# single-pwm.net
KiCad netlist of a schematic drawn in Altium Designer
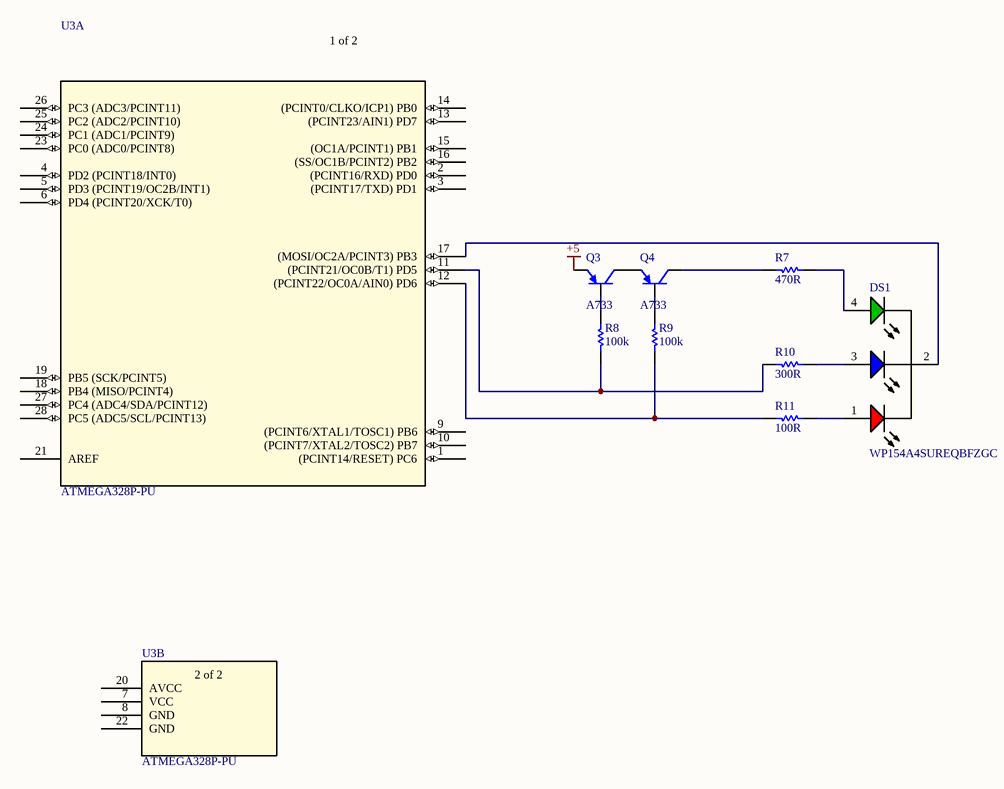
[diagram p0: single-pwm.SchDoc]

(export (version "E")
  (design (tool "Eeschema 10.0.6"))
  (components
    (comp (ref "DS1")
      (value "WP154A4SUREQBFZGC")
      (footprint "KING-WP154A4SUREQBFZGC_V")
      (description "Full Color LED Lamp, Dominant Wavelength RGB 630 / 525 / 465 nm, -40 to 85 degC, 4-Pin THD, RoHS")
      (fields (field (name "MANUFACTURER") "Kingbright"))
      (libsource (lib "Altium Content Vault") (part "LED-RGB-AKAA-4"))
    )
    (comp (ref "Q3")
      (value "A733")
      (footprint "TO-92_ONS")
      (description "PNP General Purpose Transistor")
      (fields (field (name "PUBLISHER") "Altium Limited"))
      (libsource (lib "Common Parts") (part "A733"))
    )
    (comp (ref "Q4")
      (value "A733")
      (footprint "TO-92_ONS")
      (description "PNP General Purpose Transistor")
      (fields (field (name "PUBLISHER") "Altium Limited"))
      (libsource (lib "Common Parts") (part "A733"))
    )
    (comp (ref "R7")
      (value "470R")
      (footprint "RES_TOP_1")
      (description "Resistor")
      (fields (field (name "PUBLISHER") "Altium Limited"))
      (libsource (lib "Common Parts") (part "Res1"))
    )
    (comp (ref "R8")
      (value "100k")
      (footprint "RES_TOP_1")
      (description "Resistor")
      (fields (field (name "PUBLISHER") "Altium Limited"))
      (libsource (lib "Common Parts") (part "Res1"))
    )
    (comp (ref "R9")
      (value "100k")
      (footprint "RES_TOP_1")
      (description "Resistor")
      (fields (field (name "PUBLISHER") "Altium Limited"))
      (libsource (lib "Common Parts") (part "Res1"))
    )
    (comp (ref "R10")
      (value "300R")
      (footprint "RES_TOP_1")
      (description "Resistor")
      (fields (field (name "PUBLISHER") "Altium Limited"))
      (libsource (lib "Common Parts") (part "Res1"))
    )
    (comp (ref "R11")
      (value "100R")
      (footprint "RES_TOP_1")
      (description "Resistor")
      (fields (field (name "PUBLISHER") "Altium Limited"))
      (libsource (lib "Common Parts") (part "Res1"))
    )
    (comp (ref "U3")
      (value "ATMEGA328P-PU")
      (footprint "28P3_ATM")
      (description "No Description Available")
      (fields (field (name "COPYRIGHT") "Copyright (C) 2018 Accelerated Designs. All rights reserved"))
      (libsource (lib "ul_ATMEGA328PPU") (part "ATMEGA328P-PU"))
    )
  )
  (nets
    (net (code "1") (name "+5") (class "Default")
      (node (ref "Q3") (pin "1") (pinfunction "E_1") (pintype "passive"))
    )
    (net (code "2") (name "Net-(DS1-BLUE)") (class "Default")
      (node (ref "DS1") (pin "3") (pinfunction "BLUE_3") (pintype "passive"))
      (node (ref "R10") (pin "2") (pinfunction "2_2") (pintype "passive"))
    )
    (net (code "3") (name "Net-(DS1-CATHODE)") (class "Default")
      (node (ref "DS1") (pin "2") (pinfunction "CATHODE_2") (pintype "passive"))
      (node (ref "U3") (pin "17") (pinfunction "(MOSI/OC2A/PCINT3)_PB3_17") (pintype "bidirectional"))
    )
    (net (code "4") (name "Net-(DS1-GREEN)") (class "Default")
      (node (ref "DS1") (pin "4") (pinfunction "GREEN_4") (pintype "passive"))
      (node (ref "R7") (pin "2") (pinfunction "2_2") (pintype "passive"))
    )
    (net (code "5") (name "Net-(DS1-RED)") (class "Default")
      (node (ref "DS1") (pin "1") (pinfunction "RED_1") (pintype "passive"))
      (node (ref "R11") (pin "2") (pinfunction "2_2") (pintype "passive"))
    )
    (net (code "6") (name "Net-(Q3-B)") (class "Default")
      (node (ref "Q3") (pin "3") (pinfunction "B_3") (pintype "passive"))
      (node (ref "R8") (pin "2") (pinfunction "2_2") (pintype "passive"))
    )
    (net (code "7") (name "Net-(Q3-C)") (class "Default")
      (node (ref "Q3") (pin "2") (pinfunction "C_2") (pintype "passive"))
      (node (ref "Q4") (pin "1") (pinfunction "E_1") (pintype "passive"))
    )
    (net (code "8") (name "Net-(Q4-B)") (class "Default")
      (node (ref "Q4") (pin "3") (pinfunction "B_3") (pintype "passive"))
      (node (ref "R9") (pin "2") (pinfunction "2_2") (pintype "passive"))
    )
    (net (code "9") (name "Net-(Q4-C)") (class "Default")
      (node (ref "Q4") (pin "2") (pinfunction "C_2") (pintype "passive"))
      (node (ref "R7") (pin "1") (pinfunction "1_1") (pintype "passive"))
    )
    (net (code "10") (name "Net-(U3A-(PCINT21{slash}OC0B{slash}T1)_PD5)") (class "Default")
      (node (ref "R10") (pin "1") (pinfunction "1_1") (pintype "passive"))
      (node (ref "R8") (pin "1") (pinfunction "1_1") (pintype "passive"))
      (node (ref "U3") (pin "11") (pinfunction "(PCINT21/OC0B/T1)_PD5_11") (pintype "bidirectional"))
    )
    (net (code "11") (name "Net-(U3A-(PCINT22{slash}OC0A{slash}AIN0)_PD6)") (class "Default")
      (node (ref "R11") (pin "1") (pinfunction "1_1") (pintype "passive"))
      (node (ref "R9") (pin "1") (pinfunction "1_1") (pintype "passive"))
      (node (ref "U3") (pin "12") (pinfunction "(PCINT22/OC0A/AIN0)_PD6_12") (pintype "bidirectional"))
    )
    (net (code "12") (name "unconnected-(U3A-(OC1A{slash}PCINT1)_PB1-Pad15)") (class "Default")
      (node (ref "U3") (pin "15") (pinfunction "(OC1A/PCINT1)_PB1_15") (pintype "bidirectional"))
    )
    (net (code "13") (name "unconnected-(U3A-(PCINT0{slash}CLKO{slash}ICP1)_PB0-Pad14)") (class "Default")
      (node (ref "U3") (pin "14") (pinfunction "(PCINT0/CLKO/ICP1)_PB0_14") (pintype "bidirectional"))
    )
    (net (code "14") (name "unconnected-(U3A-(PCINT6{slash}XTAL1{slash}TOSC1)_PB6-Pad9)") (class "Default")
      (node (ref "U3") (pin "9") (pinfunction "(PCINT6/XTAL1/TOSC1)_PB6_9") (pintype "bidirectional"))
    )
    (net (code "15") (name "unconnected-(U3A-(PCINT7{slash}XTAL2{slash}TOSC2)_PB7-Pad10)") (class "Default")
      (node (ref "U3") (pin "10") (pinfunction "(PCINT7/XTAL2/TOSC2)_PB7_10") (pintype "bidirectional"))
    )
    (net (code "16") (name "unconnected-(U3A-(PCINT14{slash}RESET)_PC6-Pad1)") (class "Default")
      (node (ref "U3") (pin "1") (pinfunction "(PCINT14/RESET)_PC6_1") (pintype "bidirectional"))
    )
    (net (code "17") (name "unconnected-(U3A-(PCINT16{slash}RXD)_PD0-Pad2)") (class "Default")
      (node (ref "U3") (pin "2") (pinfunction "(PCINT16/RXD)_PD0_2") (pintype "bidirectional"))
    )
    (net (code "18") (name "unconnected-(U3A-(PCINT17{slash}TXD)_PD1-Pad3)") (class "Default")
      (node (ref "U3") (pin "3") (pinfunction "(PCINT17/TXD)_PD1_3") (pintype "bidirectional"))
    )
    (net (code "19") (name "unconnected-(U3A-(PCINT23{slash}AIN1)_PD7-Pad13)") (class "Default")
      (node (ref "U3") (pin "13") (pinfunction "(PCINT23/AIN1)_PD7_13") (pintype "bidirectional"))
    )
    (net (code "20") (name "unconnected-(U3A-(SS{slash}OC1B{slash}PCINT2)_PB2-Pad16)") (class "Default")
      (node (ref "U3") (pin "16") (pinfunction "(SS/OC1B/PCINT2)_PB2_16") (pintype "bidirectional"))
    )
    (net (code "21") (name "unconnected-(U3A-AREF-Pad21)") (class "Default")
      (node (ref "U3") (pin "21") (pinfunction "AREF_21") (pintype "passive"))
    )
    (net (code "22") (name "unconnected-(U3A-PB4_(MISO{slash}PCINT4)-Pad18)") (class "Default")
      (node (ref "U3") (pin "18") (pinfunction "PB4_(MISO/PCINT4)_18") (pintype "bidirectional"))
    )
    (net (code "23") (name "unconnected-(U3A-PB5_(SCK{slash}PCINT5)-Pad19)") (class "Default")
      (node (ref "U3") (pin "19") (pinfunction "PB5_(SCK/PCINT5)_19") (pintype "bidirectional"))
    )
    (net (code "24") (name "unconnected-(U3A-PC0_(ADC0{slash}PCINT8)-Pad23)") (class "Default")
      (node (ref "U3") (pin "23") (pinfunction "PC0_(ADC0/PCINT8)_23") (pintype "bidirectional"))
    )
    (net (code "25") (name "unconnected-(U3A-PC1_(ADC1{slash}PCINT9)-Pad24)") (class "Default")
      (node (ref "U3") (pin "24") (pinfunction "PC1_(ADC1/PCINT9)_24") (pintype "bidirectional"))
    )
    (net (code "26") (name "unconnected-(U3A-PC2_(ADC2{slash}PCINT10)-Pad25)") (class "Default")
      (node (ref "U3") (pin "25") (pinfunction "PC2_(ADC2/PCINT10)_25") (pintype "bidirectional"))
    )
    (net (code "27") (name "unconnected-(U3A-PC3_(ADC3{slash}PCINT11)-Pad26)") (class "Default")
      (node (ref "U3") (pin "26") (pinfunction "PC3_(ADC3/PCINT11)_26") (pintype "bidirectional"))
    )
    (net (code "28") (name "unconnected-(U3A-PC4_(ADC4{slash}SDA{slash}PCINT12)-Pad27)") (class "Default")
      (node (ref "U3") (pin "27") (pinfunction "PC4_(ADC4/SDA/PCINT12)_27") (pintype "bidirectional"))
    )
    (net (code "29") (name "unconnected-(U3A-PC5_(ADC5{slash}SCL{slash}PCINT13)-Pad28)") (class "Default")
      (node (ref "U3") (pin "28") (pinfunction "PC5_(ADC5/SCL/PCINT13)_28") (pintype "bidirectional"))
    )
    (net (code "30") (name "unconnected-(U3A-PD2_(PCINT18{slash}INT0)-Pad4)") (class "Default")
      (node (ref "U3") (pin "4") (pinfunction "PD2_(PCINT18/INT0)_4") (pintype "bidirectional"))
    )
    (net (code "31") (name "unconnected-(U3A-PD3_(PCINT19{slash}OC2B{slash}INT1)-Pad5)") (class "Default")
      (node (ref "U3") (pin "5") (pinfunction "PD3_(PCINT19/OC2B/INT1)_5") (pintype "bidirectional"))
    )
    (net (code "32") (name "unconnected-(U3A-PD4_(PCINT20{slash}XCK{slash}T0)-Pad6)") (class "Default")
      (node (ref "U3") (pin "6") (pinfunction "PD4_(PCINT20/XCK/T0)_6") (pintype "bidirectional"))
    )
    (net (code "33") (name "unconnected-(U3B-AVCC-Pad20)") (class "Default")
      (node (ref "U3") (pin "20") (pinfunction "AVCC_20") (pintype "power_in"))
    )
    (net (code "34") (name "unconnected-(U3B-GND-Pad8)") (class "Default")
      (node (ref "U3") (pin "8") (pinfunction "GND_8") (pintype "power_in"))
    )
    (net (code "35") (name "unconnected-(U3B-GND-Pad22)") (class "Default")
      (node (ref "U3") (pin "22") (pinfunction "GND_22") (pintype "power_in"))
    )
    (net (code "36") (name "unconnected-(U3B-VCC-Pad7)") (class "Default")
      (node (ref "U3") (pin "7") (pinfunction "VCC_7") (pintype "power_in"))
    )
  )
)
